# vuMeter.net
KiCad netlist of a schematic drawn in EAGLE
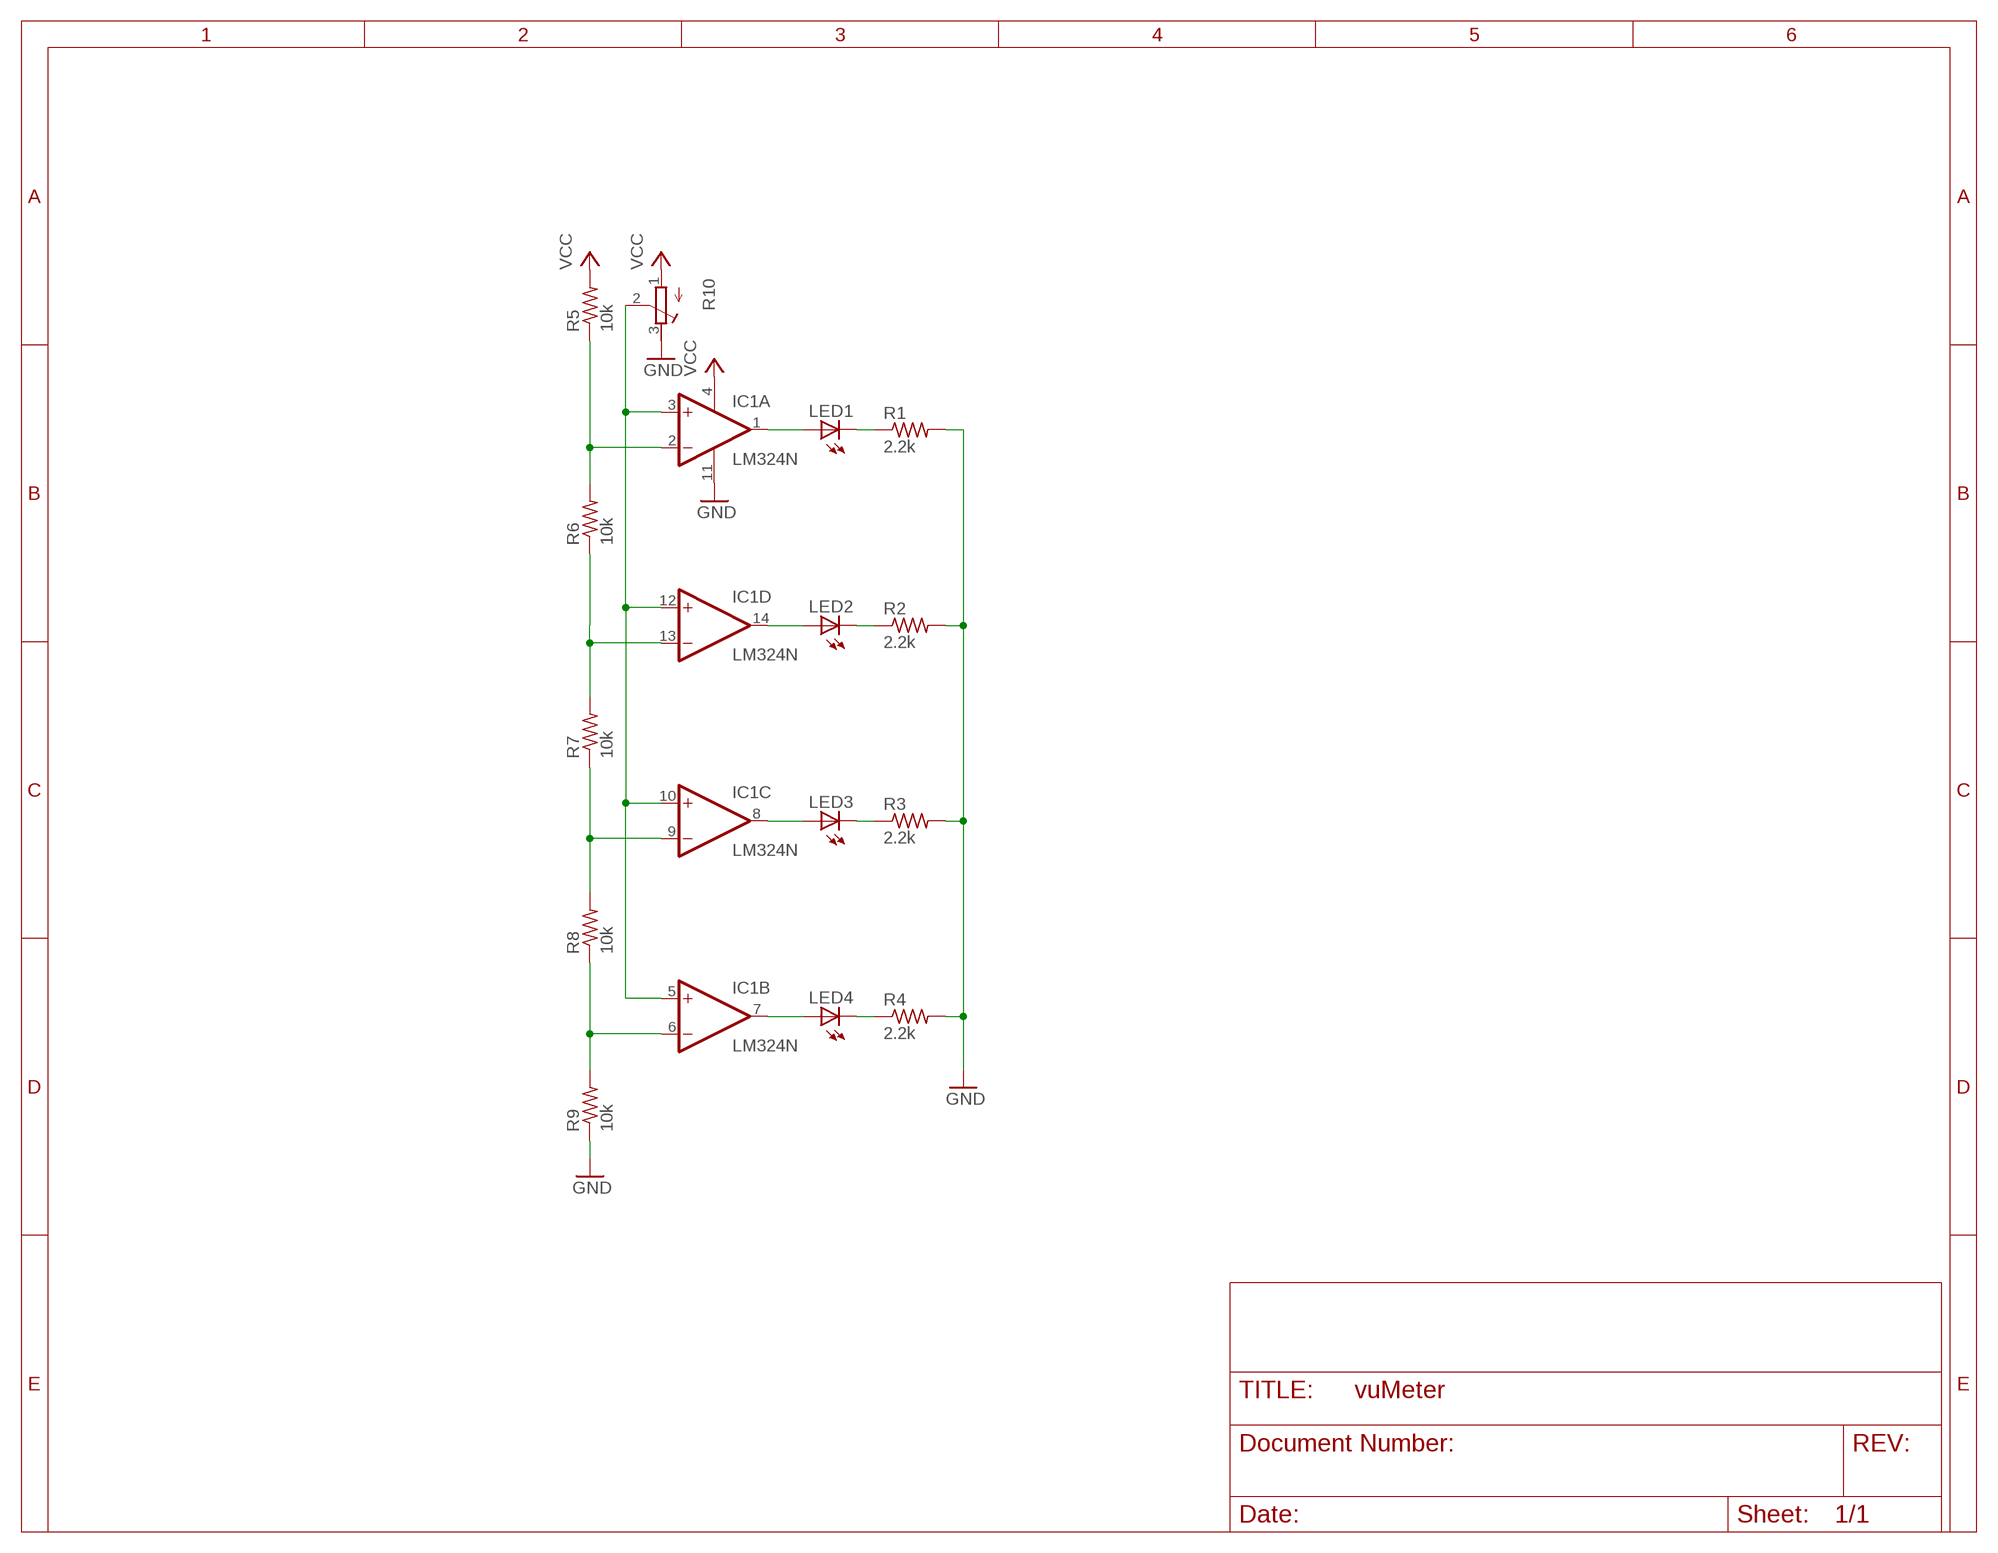
[diagram p0: schematic, sheet 1]

(export (version "E")
  (design (tool "Eeschema 10.0.6"))
  (components
    (comp (ref "IC1")
      (value "LM324N")
      (footprint "eagle-import:DIL14")
      (libsource (lib "eagle-import") (part "LM324N"))
    )
    (comp (ref "LED1")
      (value "LED5MM")
      (footprint "eagle-import:LED5MM")
      (libsource (lib "eagle-import") (part "LED5MM"))
    )
    (comp (ref "LED2")
      (value "LED5MM")
      (footprint "eagle-import:LED5MM")
      (libsource (lib "eagle-import") (part "LED5MM"))
    )
    (comp (ref "LED3")
      (value "LED5MM")
      (footprint "eagle-import:LED5MM")
      (libsource (lib "eagle-import") (part "LED5MM"))
    )
    (comp (ref "LED4")
      (value "LED5MM")
      (footprint "eagle-import:LED5MM")
      (libsource (lib "eagle-import") (part "LED5MM"))
    )
    (comp (ref "R1")
      (value "2.2k")
      (footprint "eagle-import:0207_10")
      (libsource (lib "eagle-import") (part "R-US_0207/10"))
    )
    (comp (ref "R2")
      (value "2.2k")
      (footprint "eagle-import:0207_10")
      (libsource (lib "eagle-import") (part "R-US_0207/10"))
    )
    (comp (ref "R3")
      (value "2.2k")
      (footprint "eagle-import:0207_10")
      (libsource (lib "eagle-import") (part "R-US_0207/10"))
    )
    (comp (ref "R4")
      (value "2.2k")
      (footprint "eagle-import:0207_10")
      (libsource (lib "eagle-import") (part "R-US_0207/10"))
    )
    (comp (ref "R5")
      (value "10k")
      (footprint "eagle-import:0207_10")
      (libsource (lib "eagle-import") (part "R-US_0207/10"))
    )
    (comp (ref "R6")
      (value "10k")
      (footprint "eagle-import:0207_10")
      (libsource (lib "eagle-import") (part "R-US_0207/10"))
    )
    (comp (ref "R7")
      (value "10k")
      (footprint "eagle-import:0207_10")
      (libsource (lib "eagle-import") (part "R-US_0207/10"))
    )
    (comp (ref "R8")
      (value "10k")
      (footprint "eagle-import:0207_10")
      (libsource (lib "eagle-import") (part "R-US_0207/10"))
    )
    (comp (ref "R9")
      (value "10k")
      (footprint "eagle-import:0207_10")
      (libsource (lib "eagle-import") (part "R-US_0207/10"))
    )
    (comp (ref "R10")
      (value "R-TRIMM3296W")
      (footprint "eagle-import:RTRIM3296W")
      (libsource (lib "eagle-import") (part "R-TRIMM3296W"))
    )
  )
  (nets
    (net (code "1") (name "GND") (class "Default")
      (node (ref "IC1") (pin "11") (pinfunction "V-_11") (pintype "power_in"))
      (node (ref "R1") (pin "2") (pinfunction "2_2") (pintype "passive"))
      (node (ref "R10") (pin "3") (pinfunction "E_3") (pintype "passive"))
      (node (ref "R2") (pin "2") (pinfunction "2_2") (pintype "passive"))
      (node (ref "R3") (pin "2") (pinfunction "2_2") (pintype "passive"))
      (node (ref "R4") (pin "2") (pinfunction "2_2") (pintype "passive"))
      (node (ref "R9") (pin "1") (pinfunction "1_1") (pintype "passive"))
    )
    (net (code "2") (name "Net-(IC1A-+IN)") (class "Default")
      (node (ref "IC1") (pin "10") (pinfunction "+IN_10") (pintype "input"))
      (node (ref "IC1") (pin "12") (pinfunction "+IN_12") (pintype "input"))
      (node (ref "IC1") (pin "3") (pinfunction "+IN_3") (pintype "input"))
      (node (ref "IC1") (pin "5") (pinfunction "+IN_5") (pintype "input"))
      (node (ref "R10") (pin "2") (pinfunction "S_2") (pintype "passive"))
    )
    (net (code "3") (name "Net-(IC1A--IN)") (class "Default")
      (node (ref "IC1") (pin "2") (pinfunction "-IN_2") (pintype "input"))
      (node (ref "R5") (pin "1") (pinfunction "1_1") (pintype "passive"))
      (node (ref "R6") (pin "2") (pinfunction "2_2") (pintype "passive"))
    )
    (net (code "4") (name "Net-(IC1A-OUT)") (class "Default")
      (node (ref "IC1") (pin "1") (pinfunction "OUT_1") (pintype "output"))
      (node (ref "LED1") (pin "A") (pinfunction "A_A") (pintype "passive"))
    )
    (net (code "5") (name "Net-(IC1B--IN)") (class "Default")
      (node (ref "IC1") (pin "6") (pinfunction "-IN_6") (pintype "input"))
      (node (ref "R8") (pin "1") (pinfunction "1_1") (pintype "passive"))
      (node (ref "R9") (pin "2") (pinfunction "2_2") (pintype "passive"))
    )
    (net (code "6") (name "Net-(IC1B-OUT)") (class "Default")
      (node (ref "IC1") (pin "7") (pinfunction "OUT_7") (pintype "output"))
      (node (ref "LED4") (pin "A") (pinfunction "A_A") (pintype "passive"))
    )
    (net (code "7") (name "Net-(IC1C--IN)") (class "Default")
      (node (ref "IC1") (pin "9") (pinfunction "-IN_9") (pintype "input"))
      (node (ref "R7") (pin "1") (pinfunction "1_1") (pintype "passive"))
      (node (ref "R8") (pin "2") (pinfunction "2_2") (pintype "passive"))
    )
    (net (code "8") (name "Net-(IC1C-OUT)") (class "Default")
      (node (ref "IC1") (pin "8") (pinfunction "OUT_8") (pintype "output"))
      (node (ref "LED3") (pin "A") (pinfunction "A_A") (pintype "passive"))
    )
    (net (code "9") (name "Net-(IC1D--IN)") (class "Default")
      (node (ref "IC1") (pin "13") (pinfunction "-IN_13") (pintype "input"))
      (node (ref "R6") (pin "1") (pinfunction "1_1") (pintype "passive"))
      (node (ref "R7") (pin "2") (pinfunction "2_2") (pintype "passive"))
    )
    (net (code "10") (name "Net-(IC1D-OUT)") (class "Default")
      (node (ref "IC1") (pin "14") (pinfunction "OUT_14") (pintype "output"))
      (node (ref "LED2") (pin "A") (pinfunction "A_A") (pintype "passive"))
    )
    (net (code "11") (name "Net-(LED1-C)") (class "Default")
      (node (ref "LED1") (pin "K") (pinfunction "C_K") (pintype "passive"))
      (node (ref "R1") (pin "1") (pinfunction "1_1") (pintype "passive"))
    )
    (net (code "12") (name "Net-(LED2-C)") (class "Default")
      (node (ref "LED2") (pin "K") (pinfunction "C_K") (pintype "passive"))
      (node (ref "R2") (pin "1") (pinfunction "1_1") (pintype "passive"))
    )
    (net (code "13") (name "Net-(LED3-C)") (class "Default")
      (node (ref "LED3") (pin "K") (pinfunction "C_K") (pintype "passive"))
      (node (ref "R3") (pin "1") (pinfunction "1_1") (pintype "passive"))
    )
    (net (code "14") (name "Net-(LED4-C)") (class "Default")
      (node (ref "LED4") (pin "K") (pinfunction "C_K") (pintype "passive"))
      (node (ref "R4") (pin "1") (pinfunction "1_1") (pintype "passive"))
    )
    (net (code "15") (name "VCC") (class "Default")
      (node (ref "IC1") (pin "4") (pinfunction "V+_4") (pintype "power_in"))
      (node (ref "R10") (pin "1") (pinfunction "A_1") (pintype "passive"))
      (node (ref "R5") (pin "2") (pinfunction "2_2") (pintype "passive"))
    )
  )
)
